# LC86G-PA_Breakout_Board_V2_1_easyEDA_Pro.net
KiCad netlist of a schematic drawn in EasyEDA Pro
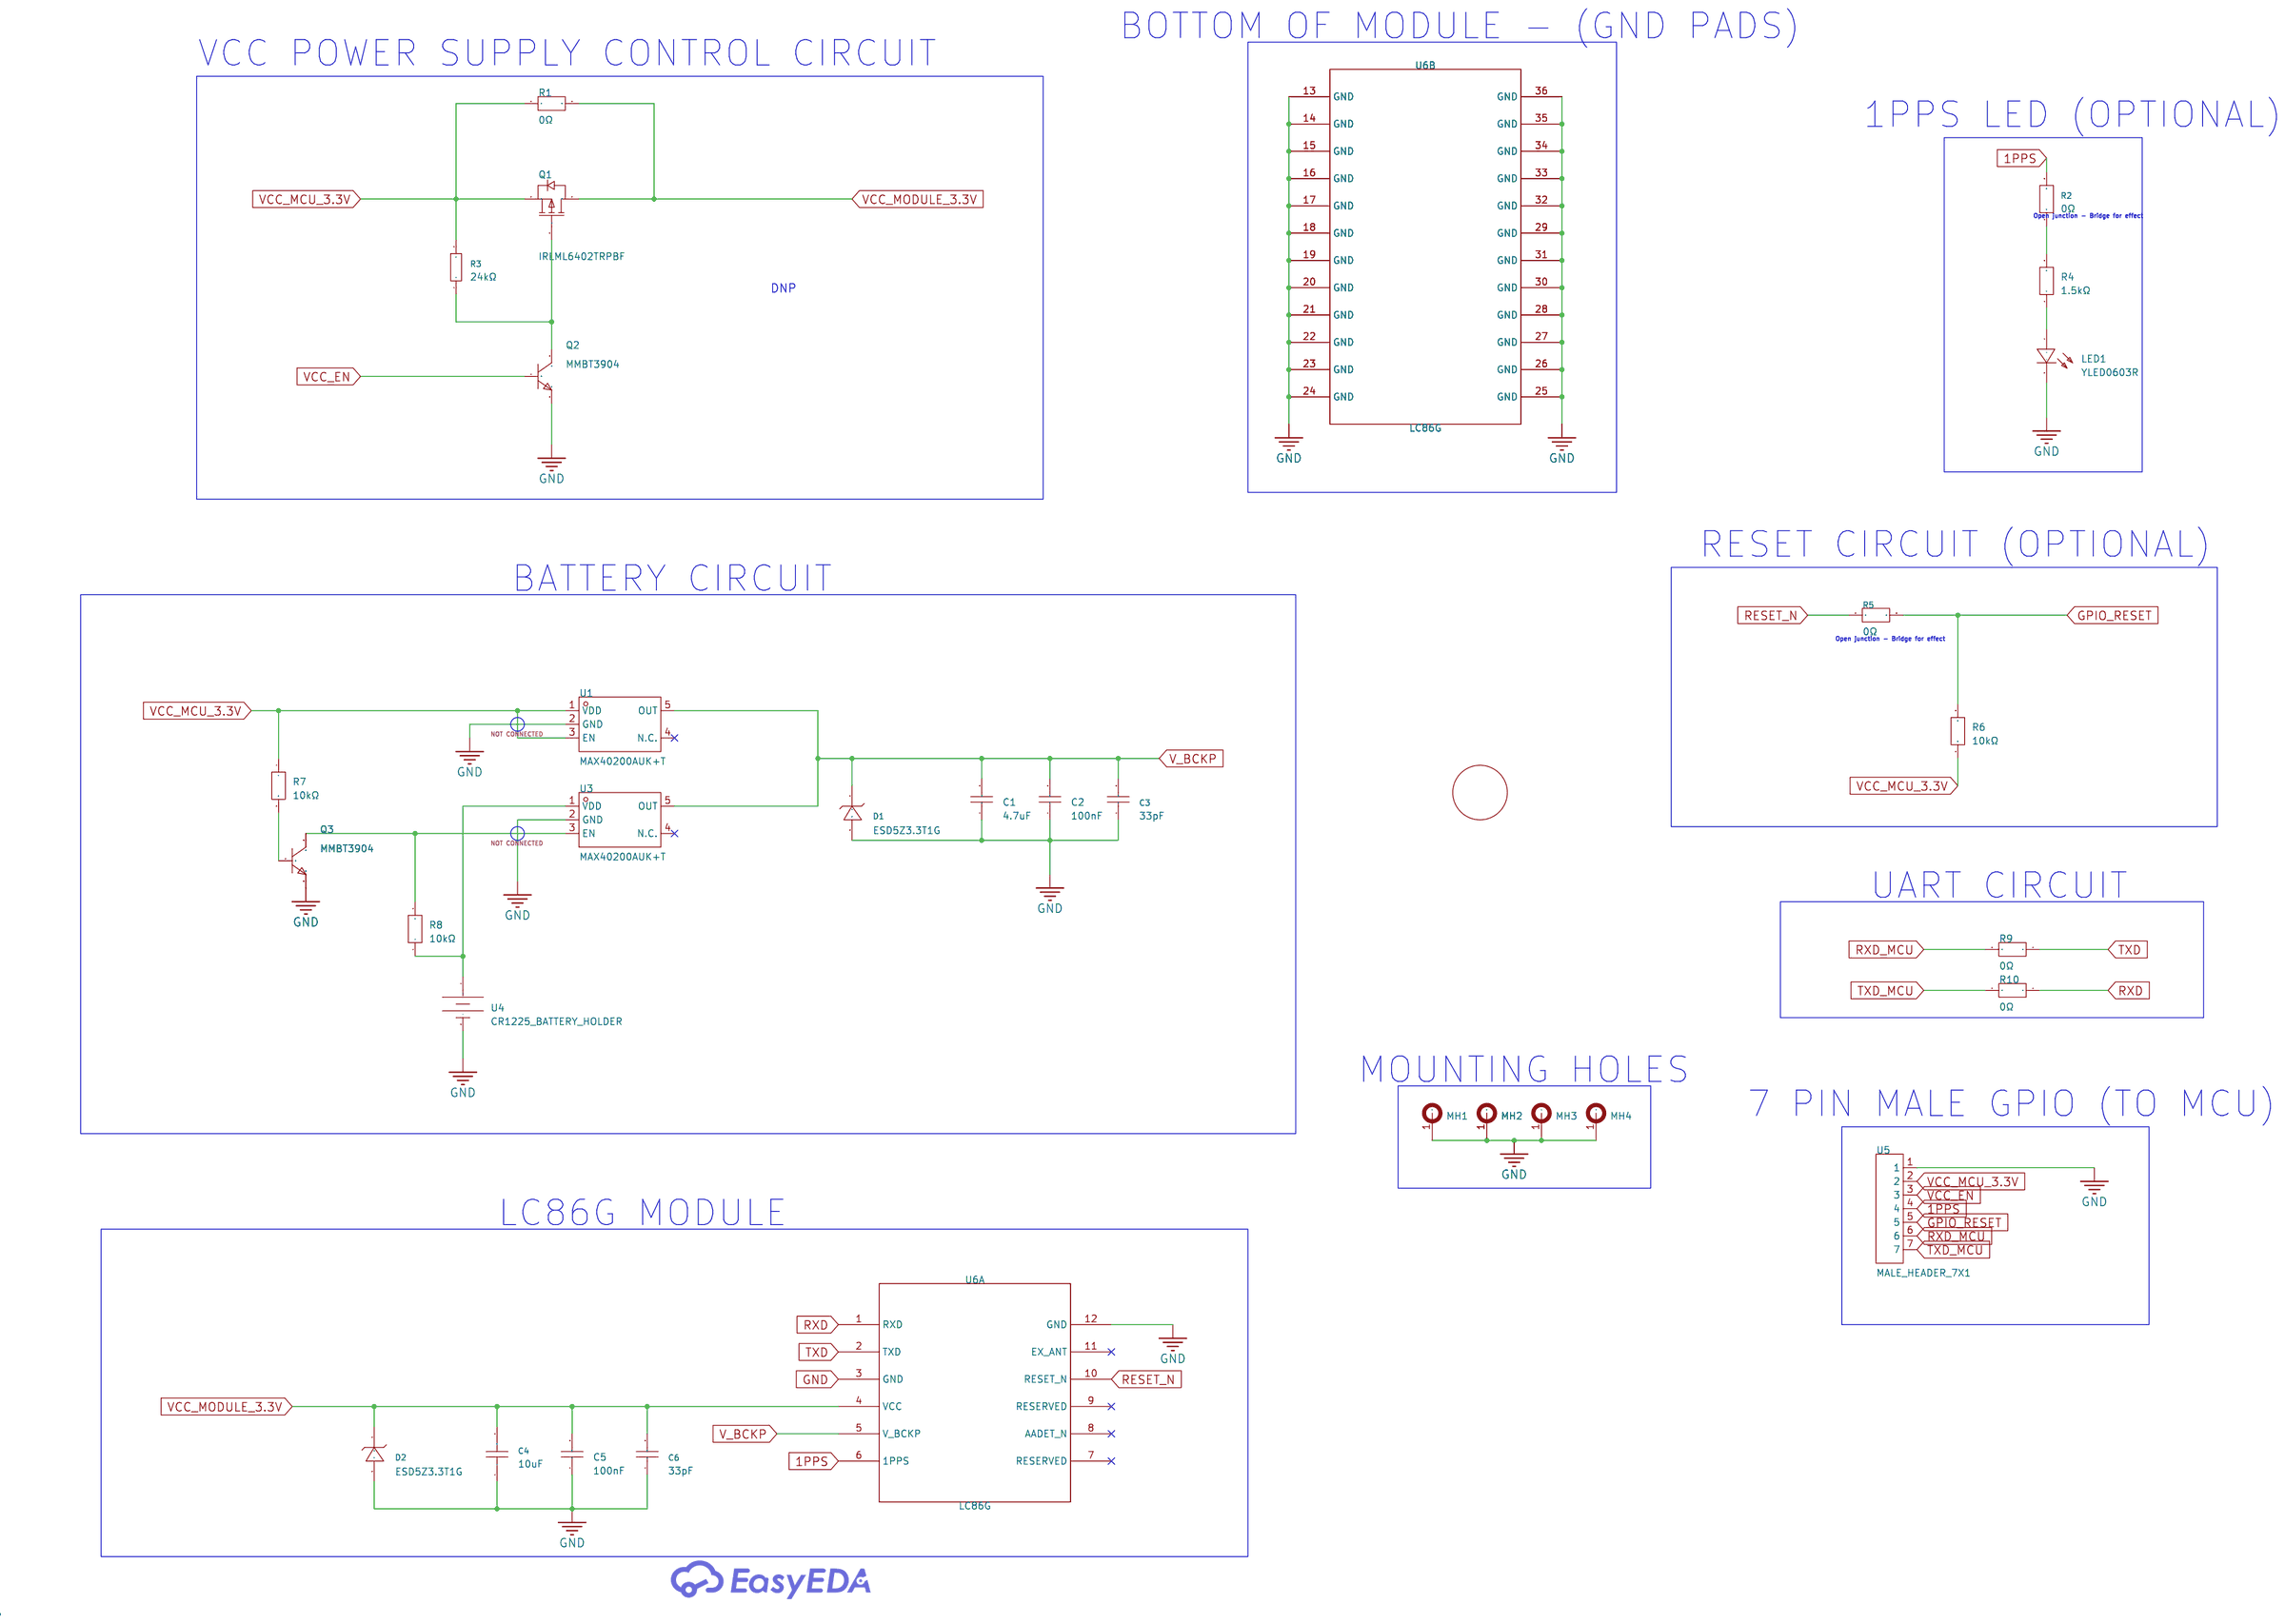
[diagram p0: schematic sheet]

(export (version "E")
  (design (tool "Eeschema 10.0.6"))
  (components
    (comp (ref "C1")
      (value "4.7uF")
      (footprint "easyedapro:C0603")
      (fields
        (field (name "Manufacturer Part") "CL10A475KA8NQNC")
        (field (name "Manufacturer") "SAMSUNG(三星)")
      )
      (libsource (lib "easyedapro") (part "CL10A475KA8NQNC"))
    )
    (comp (ref "C2")
      (value "100nF")
      (footprint "easyedapro:C0603")
      (description "Capacitance:100nF Tolerance:±10% Tolerance:±10% Voltage Rating:50V Temperature Coefficient:X7R")
      (fields (field (name "Manufacturer Part") "0603B104K500NT") (field (name "Manufacturer") "FH(风华)"))
      (libsource (lib "easyedapro") (part "0603B104K500NT"))
    )
    (comp (ref "C3")
      (value "33pF")
      (footprint "easyedapro:C0603")
      (fields
        (field (name "Manufacturer Part") "CC0603JRNPO9BN330")
        (field (name "Manufacturer") "YAGEO(国巨)")
      )
      (libsource (lib "easyedapro") (part "CC0603JRNPO9BN330"))
    )
    (comp (ref "C4")
      (value "10uF")
      (footprint "easyedapro:C0603")
      (fields
        (field (name "Manufacturer Part") "GRM188R61E106KA73D")
        (field (name "Manufacturer") "muRata(村田)")
      )
      (libsource (lib "easyedapro") (part "GRM188R61E106KA73D"))
    )
    (comp (ref "C5")
      (value "100nF")
      (footprint "easyedapro:C0603")
      (description "Capacitance:100nF Tolerance:±10% Tolerance:±10% Voltage Rating:50V Temperature Coefficient:X7R")
      (fields (field (name "Manufacturer Part") "0603B104K500NT") (field (name "Manufacturer") "FH(风华)"))
      (libsource (lib "easyedapro") (part "0603B104K500NT"))
    )
    (comp (ref "C6")
      (value "33pF")
      (footprint "easyedapro:C0603")
      (fields
        (field (name "Manufacturer Part") "CC0603JRNPO9BN330")
        (field (name "Manufacturer") "YAGEO(国巨)")
      )
      (libsource (lib "easyedapro") (part "CC0603JRNPO9BN330"))
    )
    (comp (ref "D1")
      (value "ESD5Z3.3T1G")
      (footprint "easyedapro:SOD-523F_L1.2-W0.8-LS1.7-RD")
      (fields (field (name "Manufacturer") "onsemi(安森美)"))
      (libsource (lib "easyedapro") (part "ESD5Z3.3T1G"))
    )
    (comp (ref "D2")
      (value "ESD5Z3.3T1G")
      (footprint "easyedapro:SOD-523F_L1.2-W0.8-LS1.7-RD")
      (fields (field (name "Manufacturer") "onsemi(安森美)"))
      (libsource (lib "easyedapro") (part "ESD5Z3.3T1G"))
    )
    (comp (ref "LED1")
      (value "YLED0603R")
      (footprint "easyedapro:LED0603-FD")
      (fields (field (name "Manufacturer") "YONGYUTAI(永裕泰)"))
      (libsource (lib "easyedapro") (part "YLED0603R"))
    )
    (comp (ref "MH1")
      (value "~")
      (footprint "easyedapro:MH_7.5x2.7MM")
      (libsource (lib "easyedapro") (part "MH_7.5x2.7MM"))
    )
    (comp (ref "MH2")
      (value "~")
      (footprint "easyedapro:MH_7.5x2.7MM")
      (libsource (lib "easyedapro") (part "MH_7.5x2.7MM"))
    )
    (comp (ref "MH3")
      (value "~")
      (footprint "easyedapro:MH_7.5x2.7MM")
      (libsource (lib "easyedapro") (part "MH_7.5x2.7MM"))
    )
    (comp (ref "MH4")
      (value "~")
      (footprint "easyedapro:MH_7.5x2.7MM")
      (libsource (lib "easyedapro") (part "MH_7.5x2.7MM"))
    )
    (comp (ref "Q1")
      (value "IRLML6402TRPBF")
      (footprint "easyedapro:SOT-23-3_L2.9-W1.6-P1.90-LS2.8-BR")
      (fields (field (name "Manufacturer") "Infineon(英飞凌)"))
      (libsource (lib "easyedapro") (part "IRLML6402TRPBF"))
    )
    (comp (ref "Q2")
      (value "MMBT3904")
      (footprint "easyedapro:SOT-23-3_L2.9-W1.4-P1.90-LS2.6-BR")
      (fields (field (name "Manufacturer") "IDCHIP(英锐芯)"))
      (libsource (lib "easyedapro") (part "MMBT3904_C2848176"))
    )
    (comp (ref "Q3")
      (value "MMBT3904")
      (footprint "easyedapro:SOT-23-3_L2.9-W1.4-P1.90-LS2.6-BR")
      (fields (field (name "Manufacturer") "IDCHIP(英锐芯)"))
      (libsource (lib "easyedapro") (part "MMBT3904_C2848176"))
    )
    (comp (ref "R1")
      (value "0Ω")
      (footprint "easyedapro:R0603")
      (fields (field (name "Manufacturer Part") "FRC0603F0000TS") (field (name "Manufacturer") "FOJAN(富捷)"))
      (libsource (lib "easyedapro") (part "FRC0603F0000TS"))
    )
    (comp (ref "R2")
      (value "0Ω")
      (footprint "easyedapro:R0201")
      (fields
        (field (name "Manufacturer Part") "0201WMF0000TEE")
        (field (name "Manufacturer") "UNI-ROYAL(厚声)")
      )
      (libsource (lib "easyedapro") (part "0201WMF0000TEE"))
    )
    (comp (ref "R3")
      (value "24kΩ")
      (footprint "easyedapro:R0603")
      (fields
        (field (name "Manufacturer Part") "0603WAF2402T5E")
        (field (name "Manufacturer") "UNI-ROYAL(厚声)")
      )
      (libsource (lib "easyedapro") (part "0603WAF2402T5E"))
    )
    (comp (ref "R4")
      (value "1.5kΩ")
      (footprint "easyedapro:R0603")
      (fields (field (name "Manufacturer Part") "TD03G1501BT") (field (name "Manufacturer") "FH(风华)"))
      (libsource (lib "easyedapro") (part "TD03G1501BT"))
    )
    (comp (ref "R5")
      (value "0Ω")
      (footprint "easyedapro:R0201")
      (fields
        (field (name "Manufacturer Part") "0201WMF0000TEE")
        (field (name "Manufacturer") "UNI-ROYAL(厚声)")
      )
      (libsource (lib "easyedapro") (part "0201WMF0000TEE"))
    )
    (comp (ref "R6")
      (value "10kΩ")
      (footprint "easyedapro:R0603")
      (fields (field (name "Manufacturer Part") "FRC0603J103 TS") (field (name "Manufacturer") "FOJAN(富捷)"))
      (libsource (lib "easyedapro") (part "FRC0603J103TS"))
    )
    (comp (ref "R7")
      (value "10kΩ")
      (footprint "easyedapro:R0603")
      (fields (field (name "Manufacturer Part") "FRC0603J103 TS") (field (name "Manufacturer") "FOJAN(富捷)"))
      (libsource (lib "easyedapro") (part "FRC0603J103TS"))
    )
    (comp (ref "R8")
      (value "10kΩ")
      (footprint "easyedapro:R0603")
      (fields (field (name "Manufacturer Part") "FRC0603J103 TS") (field (name "Manufacturer") "FOJAN(富捷)"))
      (libsource (lib "easyedapro") (part "FRC0603J103TS"))
    )
    (comp (ref "R9")
      (value "0Ω")
      (footprint "easyedapro:R0603")
      (fields (field (name "Manufacturer Part") "FRC0603F0000TS") (field (name "Manufacturer") "FOJAN(富捷)"))
      (libsource (lib "easyedapro") (part "FRC0603F0000TS"))
    )
    (comp (ref "R10")
      (value "0Ω")
      (footprint "easyedapro:R0603")
      (fields (field (name "Manufacturer Part") "FRC0603F0000TS") (field (name "Manufacturer") "FOJAN(富捷)"))
      (libsource (lib "easyedapro") (part "FRC0603F0000TS"))
    )
    (comp (ref "U1")
      (value "MAX40200AUK+T")
      (footprint "easyedapro:TSOT-23-5_L2.9-W1.6-P0.95-LS2.8-BL")
      (fields (field (name "Manufacturer") "ADI(亚德诺)/MAXIM(美信)"))
      (libsource (lib "easyedapro") (part "MAX40200AUK+T"))
    )
    (comp (ref "U2")
      (value "~")
      (footprint "easyedapro:KEEPOUT HOLEf")
      (libsource (lib "easyedapro") (part "KEEPOUT HOLE"))
    )
    (comp (ref "U3")
      (value "MAX40200AUK+T")
      (footprint "easyedapro:TSOT-23-5_L2.9-W1.6-P0.95-LS2.8-BL")
      (fields (field (name "Manufacturer") "ADI(亚德诺)/MAXIM(美信)"))
      (libsource (lib "easyedapro") (part "MAX40200AUK+T"))
    )
    (comp (ref "U4")
      (value "CR1225_BATTERY_HOLDER")
      (footprint "easyedapro:BAT-SMD_BS-12-B3AA011")
      (fields (field (name "Manufacturer Part") "BS-12-B3AA013") (field (name "Manufacturer") "MYOUNG(美阳)"))
      (libsource (lib "easyedapro") (part "BS-12-B3AA013"))
    )
    (comp (ref "U5")
      (value "MALE_HEADER_7X1")
      (footprint "easyedapro:HDR-TH_7P-P2.54-V-M")
      (fields
        (field (name "Manufacturer Part") "HB-PH3-25417PB2GOP")
        (field (name "Manufacturer") "HANBO(汉博)")
      )
      (libsource (lib "easyedapro") (part "HB-PH3-25417PB2GOP"))
    )
    (comp (ref "U6")
      (value "LC86G")
      (description "LC86G Module 36PIN 16X16mm H6.98mm RO")
      (fields (field (name "Manufacturer") "Quectel"))
      (libsource (lib "easyedapro") (part "LC86G"))
    )
  )
  (nets
    (net (code "1") (name "1PPS") (class "Default")
      (node (ref "R2") (pin "2") (pinfunction "2_2") (pintype "input"))
      (node (ref "U5") (pin "4") (pinfunction "4_4") (pintype "unspecified"))
      (node (ref "U6") (pin "6") (pinfunction "1PPS_6") (pintype "unspecified"))
    )
    (net (code "2") (name "GND") (class "Default")
      (node (ref "C1") (pin "1") (pinfunction "1_1") (pintype "input"))
      (node (ref "C2") (pin "1") (pinfunction "1_1") (pintype "input"))
      (node (ref "C3") (pin "1") (pinfunction "1_1") (pintype "input"))
      (node (ref "C4") (pin "1") (pinfunction "1_1") (pintype "input"))
      (node (ref "C5") (pin "1") (pinfunction "1_1") (pintype "input"))
      (node (ref "C6") (pin "1") (pinfunction "1_1") (pintype "input"))
      (node (ref "D1") (pin "2") (pinfunction "2_2") (pintype "input"))
      (node (ref "D2") (pin "2") (pinfunction "2_2") (pintype "input"))
      (node (ref "LED1") (pin "2") (pinfunction "-_2") (pintype "unspecified"))
      (node (ref "MH1") (pin "1") (pinfunction "1_1") (pintype "input"))
      (node (ref "MH2") (pin "1") (pinfunction "1_1") (pintype "input"))
      (node (ref "MH3") (pin "1") (pinfunction "1_1") (pintype "input"))
      (node (ref "MH4") (pin "1") (pinfunction "1_1") (pintype "input"))
      (node (ref "Q2") (pin "2") (pinfunction "E_2") (pintype "input"))
      (node (ref "Q3") (pin "2") (pinfunction "E_2") (pintype "input"))
      (node (ref "U1") (pin "2") (pinfunction "GND_2") (pintype "unspecified"))
      (node (ref "U3") (pin "2") (pinfunction "GND_2") (pintype "unspecified"))
      (node (ref "U4") (pin "2") (pinfunction "-_2") (pintype "unspecified"))
      (node (ref "U5") (pin "1") (pinfunction "1_1") (pintype "unspecified"))
      (node (ref "U6") (pin "12") (pinfunction "GND_12") (pintype "unspecified"))
      (node (ref "U6") (pin "13") (pinfunction "GND_13") (pintype "unspecified"))
      (node (ref "U6") (pin "14") (pinfunction "GND_14") (pintype "unspecified"))
      (node (ref "U6") (pin "15") (pinfunction "GND_15") (pintype "unspecified"))
      (node (ref "U6") (pin "16") (pinfunction "GND_16") (pintype "unspecified"))
      (node (ref "U6") (pin "17") (pinfunction "GND_17") (pintype "unspecified"))
      (node (ref "U6") (pin "18") (pinfunction "GND_18") (pintype "unspecified"))
      (node (ref "U6") (pin "19") (pinfunction "GND_19") (pintype "unspecified"))
      (node (ref "U6") (pin "20") (pinfunction "GND_20") (pintype "unspecified"))
      (node (ref "U6") (pin "21") (pinfunction "GND_21") (pintype "unspecified"))
      (node (ref "U6") (pin "22") (pinfunction "GND_22") (pintype "unspecified"))
      (node (ref "U6") (pin "23") (pinfunction "GND_23") (pintype "unspecified"))
      (node (ref "U6") (pin "24") (pinfunction "GND_24") (pintype "unspecified"))
      (node (ref "U6") (pin "25") (pinfunction "GND_25") (pintype "unspecified"))
      (node (ref "U6") (pin "26") (pinfunction "GND_26") (pintype "unspecified"))
      (node (ref "U6") (pin "27") (pinfunction "GND_27") (pintype "unspecified"))
      (node (ref "U6") (pin "28") (pinfunction "GND_28") (pintype "unspecified"))
      (node (ref "U6") (pin "29") (pinfunction "GND_29") (pintype "unspecified"))
      (node (ref "U6") (pin "3") (pinfunction "GND_3") (pintype "unspecified"))
      (node (ref "U6") (pin "30") (pinfunction "GND_30") (pintype "unspecified"))
      (node (ref "U6") (pin "31") (pinfunction "GND_31") (pintype "unspecified"))
      (node (ref "U6") (pin "32") (pinfunction "GND_32") (pintype "unspecified"))
      (node (ref "U6") (pin "33") (pinfunction "GND_33") (pintype "unspecified"))
      (node (ref "U6") (pin "34") (pinfunction "GND_34") (pintype "unspecified"))
      (node (ref "U6") (pin "35") (pinfunction "GND_35") (pintype "unspecified"))
      (node (ref "U6") (pin "36") (pinfunction "GND_36") (pintype "unspecified"))
    )
    (net (code "3") (name "GPIO_RESET") (class "Default")
      (node (ref "R5") (pin "2") (pinfunction "2_2") (pintype "input"))
      (node (ref "R6") (pin "2") (pinfunction "2_2") (pintype "unspecified"))
      (node (ref "U5") (pin "5") (pinfunction "5_5") (pintype "unspecified"))
    )
    (net (code "4") (name "Net-(LED1-+)") (class "Default")
      (node (ref "LED1") (pin "1") (pinfunction "+_1") (pintype "unspecified"))
      (node (ref "R4") (pin "1") (pinfunction "1_1") (pintype "unspecified"))
    )
    (net (code "5") (name "Net-(Q1-G)") (class "Default")
      (node (ref "Q1") (pin "1") (pinfunction "G_1") (pintype "unspecified"))
      (node (ref "Q2") (pin "3") (pinfunction "C_3") (pintype "input"))
      (node (ref "R3") (pin "1") (pinfunction "1_1") (pintype "input"))
    )
    (net (code "6") (name "Net-(Q3-B)") (class "Default")
      (node (ref "Q3") (pin "1") (pinfunction "B_1") (pintype "input"))
      (node (ref "R7") (pin "2") (pinfunction "2_2") (pintype "unspecified"))
    )
    (net (code "7") (name "Net-(Q3-C)") (class "Default")
      (node (ref "Q3") (pin "3") (pinfunction "C_3") (pintype "input"))
      (node (ref "R8") (pin "2") (pinfunction "2_2") (pintype "unspecified"))
      (node (ref "U3") (pin "3") (pinfunction "EN_3") (pintype "unspecified"))
    )
    (net (code "8") (name "Net-(R2-Pad1)") (class "Default")
      (node (ref "R2") (pin "1") (pinfunction "1_1") (pintype "input"))
      (node (ref "R4") (pin "2") (pinfunction "2_2") (pintype "unspecified"))
    )
    (net (code "9") (name "Net-(U3-VDD)") (class "Default")
      (node (ref "R8") (pin "1") (pinfunction "1_1") (pintype "unspecified"))
      (node (ref "U3") (pin "1") (pinfunction "VDD_1") (pintype "unspecified"))
      (node (ref "U4") (pin "1") (pinfunction "+_1") (pintype "unspecified"))
    )
    (net (code "10") (name "RESET_N") (class "Default")
      (node (ref "R5") (pin "1") (pinfunction "1_1") (pintype "input"))
      (node (ref "U6") (pin "10") (pinfunction "RESET_N_10") (pintype "unspecified"))
    )
    (net (code "11") (name "RXD") (class "Default")
      (node (ref "R10") (pin "1") (pinfunction "1_1") (pintype "unspecified"))
      (node (ref "U6") (pin "1") (pinfunction "RXD_1") (pintype "unspecified"))
    )
    (net (code "12") (name "RXD_MCU") (class "Default")
      (node (ref "R9") (pin "2") (pinfunction "2_2") (pintype "unspecified"))
      (node (ref "U5") (pin "6") (pinfunction "6_6") (pintype "unspecified"))
    )
    (net (code "13") (name "TXD") (class "Default")
      (node (ref "R9") (pin "1") (pinfunction "1_1") (pintype "unspecified"))
      (node (ref "U6") (pin "2") (pinfunction "TXD_2") (pintype "unspecified"))
    )
    (net (code "14") (name "TXD_MCU") (class "Default")
      (node (ref "R10") (pin "2") (pinfunction "2_2") (pintype "unspecified"))
      (node (ref "U5") (pin "7") (pinfunction "7_7") (pintype "unspecified"))
    )
    (net (code "15") (name "VCC_EN") (class "Default")
      (node (ref "Q2") (pin "1") (pinfunction "B_1") (pintype "input"))
      (node (ref "U5") (pin "3") (pinfunction "3_3") (pintype "unspecified"))
    )
    (net (code "16") (name "VCC_MCU_3.3V") (class "Default")
      (node (ref "Q1") (pin "2") (pinfunction "S_2") (pintype "unspecified"))
      (node (ref "R1") (pin "2") (pinfunction "2_2") (pintype "unspecified"))
      (node (ref "R3") (pin "2") (pinfunction "2_2") (pintype "input"))
      (node (ref "R6") (pin "1") (pinfunction "1_1") (pintype "unspecified"))
      (node (ref "R7") (pin "1") (pinfunction "1_1") (pintype "unspecified"))
      (node (ref "U1") (pin "1") (pinfunction "VDD_1") (pintype "unspecified"))
      (node (ref "U1") (pin "3") (pinfunction "EN_3") (pintype "unspecified"))
      (node (ref "U5") (pin "2") (pinfunction "2_2") (pintype "unspecified"))
    )
    (net (code "17") (name "VCC_MODULE_3.3V") (class "Default")
      (node (ref "C4") (pin "2") (pinfunction "2_2") (pintype "input"))
      (node (ref "C5") (pin "2") (pinfunction "2_2") (pintype "input"))
      (node (ref "C6") (pin "2") (pinfunction "2_2") (pintype "input"))
      (node (ref "D2") (pin "1") (pinfunction "1_1") (pintype "input"))
      (node (ref "Q1") (pin "3") (pinfunction "D_3") (pintype "unspecified"))
      (node (ref "R1") (pin "1") (pinfunction "1_1") (pintype "unspecified"))
      (node (ref "U6") (pin "4") (pinfunction "VCC_4") (pintype "unspecified"))
    )
    (net (code "18") (name "V_BCKP") (class "Default")
      (node (ref "C1") (pin "2") (pinfunction "2_2") (pintype "input"))
      (node (ref "C2") (pin "2") (pinfunction "2_2") (pintype "input"))
      (node (ref "C3") (pin "2") (pinfunction "2_2") (pintype "input"))
      (node (ref "D1") (pin "1") (pinfunction "1_1") (pintype "input"))
      (node (ref "U1") (pin "5") (pinfunction "OUT_5") (pintype "unspecified"))
      (node (ref "U3") (pin "5") (pinfunction "OUT_5") (pintype "unspecified"))
      (node (ref "U6") (pin "5") (pinfunction "V_BCKP_5") (pintype "unspecified"))
    )
    (net (code "19") (name "unconnected-(U1-N.C.-Pad4)") (class "Default")
      (node (ref "U1") (pin "4") (pinfunction "N.C._4") (pintype "unspecified+no_connect"))
    )
    (net (code "20") (name "unconnected-(U3-N.C.-Pad4)") (class "Default")
      (node (ref "U3") (pin "4") (pinfunction "N.C._4") (pintype "unspecified+no_connect"))
    )
    (net (code "21") (name "unconnected-(U6A-AADET_N-Pad8)") (class "Default")
      (node (ref "U6") (pin "8") (pinfunction "AADET_N_8") (pintype "unspecified+no_connect"))
    )
    (net (code "22") (name "unconnected-(U6A-EX_ANT-Pad11)") (class "Default")
      (node (ref "U6") (pin "11") (pinfunction "EX_ANT_11") (pintype "unspecified+no_connect"))
    )
    (net (code "23") (name "unconnected-(U6A-RESERVED-Pad7)") (class "Default")
      (node (ref "U6") (pin "7") (pinfunction "RESERVED_7") (pintype "unspecified+no_connect"))
    )
    (net (code "24") (name "unconnected-(U6A-RESERVED-Pad9)") (class "Default")
      (node (ref "U6") (pin "9") (pinfunction "RESERVED_9") (pintype "unspecified+no_connect"))
    )
  )
)
